# mqtt-LightbulbwithtempandIR.net
KiCad netlist of a schematic drawn in EAGLE
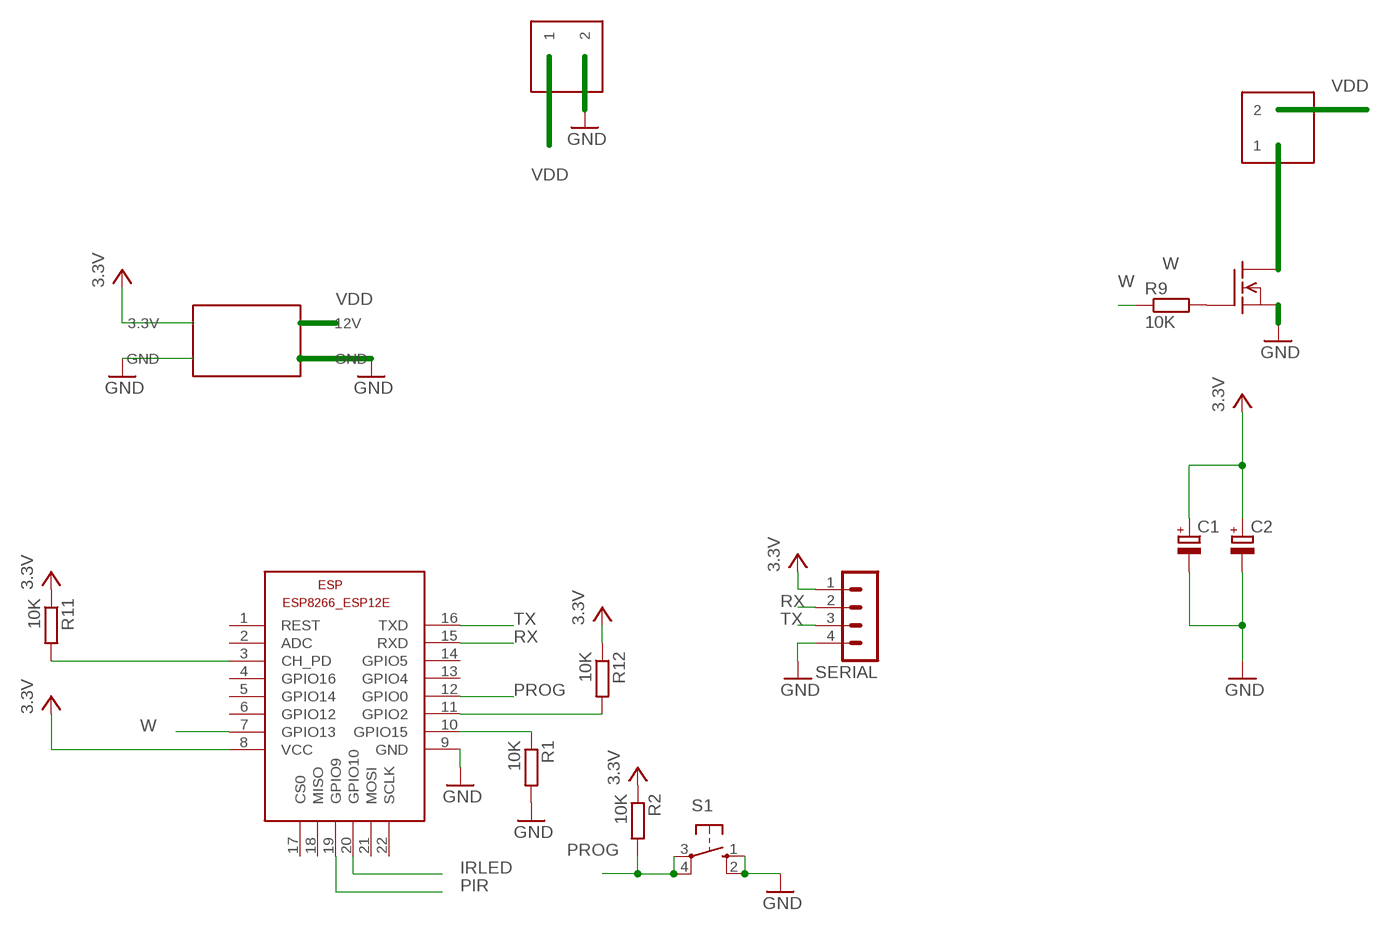
[diagram p0: schematic, sheet 1]

(export (version "E")
  (design (tool "Eeschema 10.0.6"))
  (components
    (comp (ref "C1")
      (value "CPOL-EUE2-5")
      (footprint "eagle-import:E2-5")
      (libsource (lib "eagle-import") (part "CPOL-EUE2-5"))
    )
    (comp (ref "C2")
      (value "CPOL-EUE2-5")
      (footprint "eagle-import:E2-5")
      (libsource (lib "eagle-import") (part "CPOL-EUE2-5"))
    )
    (comp (ref "ESP")
      (value "ESP8266-12EESP8266-ESP12E")
      (footprint "eagle-import:ESP8266-ESP12E")
      (libsource (lib "eagle-import") (part "ESP8266-12EESP8266-ESP12E"))
    )
    (comp (ref "PWR1")
      (value "MP2307-MINI-360")
      (footprint "eagle-import:MP2307-MINI-360")
      (libsource (lib "eagle-import") (part "MP2307-MINI-360"))
    )
    (comp (ref "PWR_IN1")
      (value "KF350-P2")
      (footprint "eagle-import:KF350-2P")
      (libsource (lib "eagle-import") (part "KF350-P2"))
    )
    (comp (ref "PWR_IN2")
      (value "KF350-P2")
      (footprint "eagle-import:KF350-2P")
      (libsource (lib "eagle-import") (part "KF350-P2"))
    )
    (comp (ref "R1")
      (value "10K")
      (footprint "eagle-import:R0603")
      (libsource (lib "eagle-import") (part "R-EU_R0603"))
    )
    (comp (ref "R2")
      (value "10K")
      (footprint "eagle-import:R0603")
      (libsource (lib "eagle-import") (part "R-EU_R0603"))
    )
    (comp (ref "R9")
      (value "10K")
      (footprint "eagle-import:R0603")
      (libsource (lib "eagle-import") (part "R-EU_R0603"))
    )
    (comp (ref "R11")
      (value "10K")
      (footprint "eagle-import:R0603")
      (libsource (lib "eagle-import") (part "R-EU_R0603"))
    )
    (comp (ref "R12")
      (value "10K")
      (footprint "eagle-import:R0603")
      (libsource (lib "eagle-import") (part "R-EU_R0603"))
    )
    (comp (ref "S1")
      (value "10-XX")
      (footprint "eagle-import:B3F-10XX")
      (fields (field (name "MPN") "B3F-1000"))
      (libsource (lib "eagle-import") (part "10-XX"))
    )
    (comp (ref "SERIAL")
      (value "MA04-1")
      (footprint "eagle-import:MA04-1")
      (libsource (lib "eagle-import") (part "MA04-1"))
    )
    (comp (ref "W")
      (value "FDS5680")
      (footprint "eagle-import:SO-8")
      (libsource (lib "eagle-import") (part "FDS5680"))
    )
  )
  (nets
    (net (code "1") (name "/IRLED") (class "Default")
      (node (ref "ESP") (pin "20") (pinfunction "GPIO10_20") (pintype "bidirectional"))
    )
    (net (code "2") (name "/PIR") (class "Default")
      (node (ref "ESP") (pin "19") (pinfunction "GPIO9_19") (pintype "bidirectional"))
    )
    (net (code "3") (name "/PROG") (class "Default")
      (node (ref "ESP") (pin "12") (pinfunction "GPIO0_12") (pintype "bidirectional"))
      (node (ref "R2") (pin "2") (pinfunction "2_2") (pintype "passive"))
      (node (ref "S1") (pin "3") (pinfunction "P_3") (pintype "passive"))
      (node (ref "S1") (pin "4") (pinfunction "P1_4") (pintype "passive"))
    )
    (net (code "4") (name "/RX") (class "Default")
      (node (ref "ESP") (pin "15") (pinfunction "RXD_15") (pintype "bidirectional"))
      (node (ref "SERIAL") (pin "2") (pinfunction "2_2") (pintype "passive"))
    )
    (net (code "5") (name "/TX") (class "Default")
      (node (ref "ESP") (pin "16") (pinfunction "TXD_16") (pintype "bidirectional"))
      (node (ref "SERIAL") (pin "3") (pinfunction "3_3") (pintype "passive"))
    )
    (net (code "6") (name "/VDD") (class "Default")
      (node (ref "PWR1") (pin "12V") (pinfunction "12V_12V") (pintype "power_in"))
      (node (ref "PWR_IN1") (pin "2") (pinfunction "2_2") (pintype "bidirectional"))
      (node (ref "PWR_IN2") (pin "1") (pinfunction "1_1") (pintype "bidirectional"))
    )
    (net (code "7") (name "/W") (class "Default")
      (node (ref "ESP") (pin "7") (pinfunction "GPIO13_7") (pintype "bidirectional"))
      (node (ref "R9") (pin "1") (pinfunction "1_1") (pintype "passive"))
    )
    (net (code "8") (name "3.3V") (class "Default")
      (node (ref "C1") (pin "+") (pinfunction "+_+") (pintype "passive"))
      (node (ref "C2") (pin "+") (pinfunction "+_+") (pintype "passive"))
      (node (ref "ESP") (pin "8") (pinfunction "VCC_8") (pintype "bidirectional"))
      (node (ref "PWR1") (pin "3.3V") (pinfunction "3.3V_3.3V") (pintype "power_in"))
      (node (ref "R11") (pin "1") (pinfunction "1_1") (pintype "passive"))
      (node (ref "R12") (pin "1") (pinfunction "1_1") (pintype "passive"))
      (node (ref "R2") (pin "1") (pinfunction "1_1") (pintype "passive"))
      (node (ref "SERIAL") (pin "1") (pinfunction "1_1") (pintype "passive"))
    )
    (net (code "9") (name "GND") (class "Default")
      (node (ref "C1") (pin "-") (pinfunction "-_-") (pintype "passive"))
      (node (ref "C2") (pin "-") (pinfunction "-_-") (pintype "passive"))
      (node (ref "ESP") (pin "9") (pinfunction "GND_9") (pintype "bidirectional"))
      (node (ref "PWR1") (pin "GND@1") (pinfunction "GND_GND@1") (pintype "power_in"))
      (node (ref "PWR1") (pin "GND@2") (pinfunction "GND_GND@2") (pintype "power_in"))
      (node (ref "PWR_IN2") (pin "2") (pinfunction "2_2") (pintype "bidirectional"))
      (node (ref "R1") (pin "2") (pinfunction "2_2") (pintype "passive"))
      (node (ref "S1") (pin "1") (pinfunction "S_1") (pintype "passive"))
      (node (ref "S1") (pin "2") (pinfunction "S1_2") (pintype "passive"))
      (node (ref "SERIAL") (pin "4") (pinfunction "4_4") (pintype "passive"))
      (node (ref "W") (pin "1") (pinfunction "S_1") (pintype "passive"))
      (node (ref "W") (pin "2") (pinfunction "S_2") (pintype "passive"))
      (node (ref "W") (pin "3") (pinfunction "S_3") (pintype "passive"))
    )
    (net (code "10") (name "Net-(ESP-CH_PD)") (class "Default")
      (node (ref "ESP") (pin "3") (pinfunction "CH_PD_3") (pintype "bidirectional"))
      (node (ref "R11") (pin "2") (pinfunction "2_2") (pintype "passive"))
    )
    (net (code "11") (name "Net-(ESP-GPIO2)") (class "Default")
      (node (ref "ESP") (pin "11") (pinfunction "GPIO2_11") (pintype "bidirectional"))
      (node (ref "R12") (pin "2") (pinfunction "2_2") (pintype "passive"))
    )
    (net (code "12") (name "Net-(ESP-GPIO15)") (class "Default")
      (node (ref "ESP") (pin "10") (pinfunction "GPIO15_10") (pintype "bidirectional"))
      (node (ref "R1") (pin "1") (pinfunction "1_1") (pintype "passive"))
    )
    (net (code "13") (name "Net-(PWR_IN1-Pad1)") (class "Default")
      (node (ref "PWR_IN1") (pin "1") (pinfunction "1_1") (pintype "bidirectional"))
      (node (ref "W") (pin "5") (pinfunction "D_5") (pintype "passive"))
      (node (ref "W") (pin "6") (pinfunction "D_6") (pintype "passive"))
      (node (ref "W") (pin "7") (pinfunction "D_7") (pintype "passive"))
      (node (ref "W") (pin "8") (pinfunction "D_8") (pintype "passive"))
    )
    (net (code "14") (name "Net-(W-G)") (class "Default")
      (node (ref "R9") (pin "2") (pinfunction "2_2") (pintype "passive"))
      (node (ref "W") (pin "4") (pinfunction "G_4") (pintype "passive"))
    )
    (net (code "15") (name "unconnected-(ESP-ADC-Pad2)") (class "Default")
      (node (ref "ESP") (pin "2") (pinfunction "ADC_2") (pintype "bidirectional"))
    )
    (net (code "16") (name "unconnected-(ESP-CS0-Pad17)") (class "Default")
      (node (ref "ESP") (pin "17") (pinfunction "CS0_17") (pintype "bidirectional"))
    )
    (net (code "17") (name "unconnected-(ESP-GPIO4-Pad13)") (class "Default")
      (node (ref "ESP") (pin "13") (pinfunction "GPIO4_13") (pintype "bidirectional"))
    )
    (net (code "18") (name "unconnected-(ESP-GPIO5-Pad14)") (class "Default")
      (node (ref "ESP") (pin "14") (pinfunction "GPIO5_14") (pintype "bidirectional"))
    )
    (net (code "19") (name "unconnected-(ESP-GPIO12-Pad6)") (class "Default")
      (node (ref "ESP") (pin "6") (pinfunction "GPIO12_6") (pintype "bidirectional"))
    )
    (net (code "20") (name "unconnected-(ESP-GPIO14-Pad5)") (class "Default")
      (node (ref "ESP") (pin "5") (pinfunction "GPIO14_5") (pintype "bidirectional"))
    )
    (net (code "21") (name "unconnected-(ESP-GPIO16-Pad4)") (class "Default")
      (node (ref "ESP") (pin "4") (pinfunction "GPIO16_4") (pintype "bidirectional"))
    )
    (net (code "22") (name "unconnected-(ESP-MISO-Pad18)") (class "Default")
      (node (ref "ESP") (pin "18") (pinfunction "MISO_18") (pintype "bidirectional"))
    )
    (net (code "23") (name "unconnected-(ESP-MOSI-Pad21)") (class "Default")
      (node (ref "ESP") (pin "21") (pinfunction "MOSI_21") (pintype "bidirectional"))
    )
    (net (code "24") (name "unconnected-(ESP-REST-Pad1)") (class "Default")
      (node (ref "ESP") (pin "1") (pinfunction "REST_1") (pintype "bidirectional"))
    )
    (net (code "25") (name "unconnected-(ESP-SCLK-Pad22)") (class "Default")
      (node (ref "ESP") (pin "22") (pinfunction "SCLK_22") (pintype "bidirectional"))
    )
  )
)
